# design.net
KiCad netlist of a schematic drawn in Altium Designer
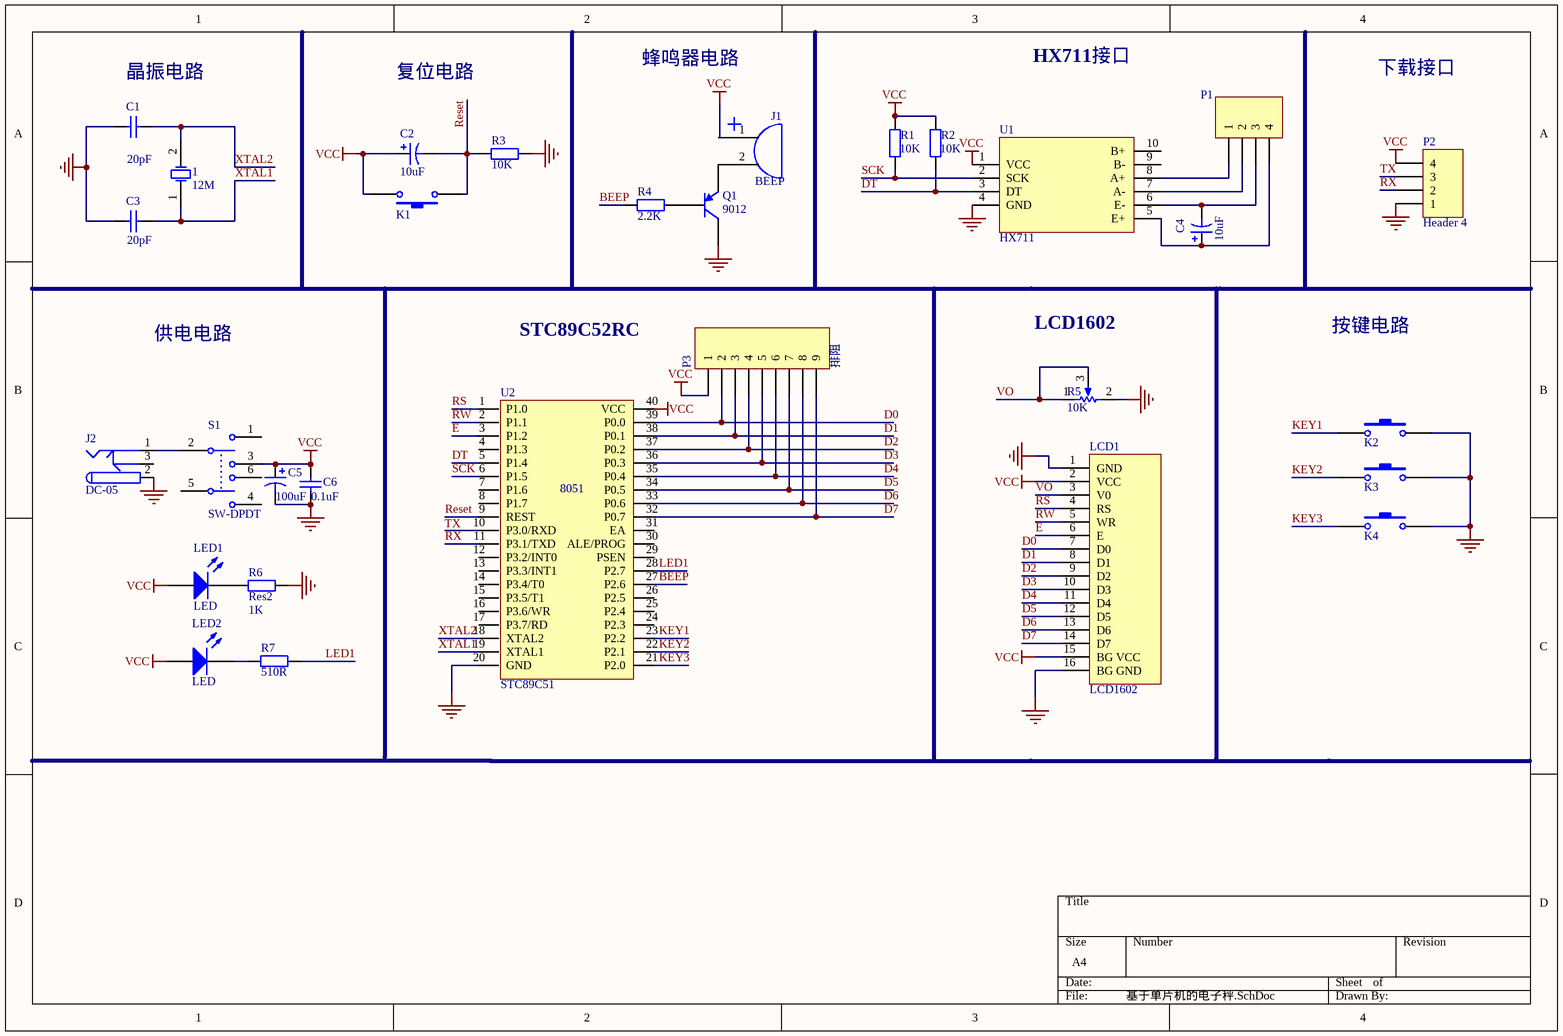
[diagram p0: 基于单片机的电子秤.SchDoc]

(export (version "E")
  (design (tool "Eeschema 10.0.6"))
  (components
    (comp (ref "1")
      (value "12M")
      (footprint "XTAL_US")
      (description "Crystal Oscillator")
      (fields (field (name "PUBLISHER") "Altium Limited"))
      (libsource (lib "Miscellaneous Devices") (part "XTAL"))
    )
    (comp (ref "C1")
      (value "20pF")
      (footprint "RAD-0.1")
      (description "Capacitor")
      (fields (field (name "Comment") "Cap") (field (name "PUBLISHER") "Altium Limited"))
      (libsource (lib "Miscellaneous Devices") (part "Cap"))
    )
    (comp (ref "C2")
      (value "10uF")
      (footprint "RB.1/.2")
      (description "Polarized Capacitor (Radial)")
      (fields (field (name "Comment") "Cap Pol1") (field (name "PUBLISHER") "Altium Limited"))
      (libsource (lib "Miscellaneous Devices") (part "Cap Pol1"))
    )
    (comp (ref "C3")
      (value "20pF")
      (footprint "RAD-0.1")
      (description "Capacitor")
      (fields (field (name "Comment") "Cap") (field (name "PUBLISHER") "Altium Limited"))
      (libsource (lib "Miscellaneous Devices") (part "Cap"))
    )
    (comp (ref "C4")
      (value "10uF")
      (footprint "RB7.6-15")
      (description "Polarized Capacitor (Radial)")
      (fields (field (name "Comment") "Cap Pol1") (field (name "PUBLISHER") "Altium Limited"))
      (libsource (lib "Miscellaneous Devices") (part "Cap Pol1"))
    )
    (comp (ref "C5")
      (value "100uF")
      (footprint "RB.1/.2")
      (description "Polarized Capacitor (Radial)")
      (fields (field (name "Comment") "Cap Pol1") (field (name "PUBLISHER") "Altium Limited"))
      (libsource (lib "Miscellaneous Devices") (part "Cap Pol1"))
    )
    (comp (ref "C6")
      (value "0.1uF")
      (footprint "RAD-0.1")
      (description "Capacitor")
      (fields (field (name "Comment") "Cap") (field (name "PUBLISHER") "Altium Limited"))
      (libsource (lib "Miscellaneous Devices") (part "Cap"))
    )
    (comp (ref "J1")
      (value "BEEP")
      (footprint "Beep")
      (description "蜂鸣器")
      (libsource (lib "Fszhang") (part "BEEP"))
    )
    (comp (ref "J2") (value "DC-05") (footprint "DC-05") (libsource (lib "My library") (part "DC-05")))
    (comp (ref "K1") (value "四脚按键") (footprint "四脚按键") (libsource (lib "My library") (part "四脚按键")))
    (comp (ref "K2") (value "四脚按键") (footprint "四脚按键") (libsource (lib "My library") (part "四脚按键")))
    (comp (ref "K3") (value "四脚按键") (footprint "四脚按键") (libsource (lib "My library") (part "四脚按键")))
    (comp (ref "K4") (value "四脚按键") (footprint "四脚按键") (libsource (lib "My library") (part "四脚按键")))
    (comp (ref "LCD1")
      (value "LCD1602")
      (footprint "LCD1602")
      (libsource (lib "My library") (part "LCD1602"))
    )
    (comp (ref "LED1") (value "LED") (footprint "LED") (libsource (lib "My library") (part "LED")))
    (comp (ref "LED2") (value "LED") (footprint "LED") (libsource (lib "My library") (part "LED")))
    (comp (ref "P1")
      (value "Header 4")
      (footprint "HDR4X1_B1")
      (description "接插件")
      (fields (field (name "PUBLISHER") "Altium Limited"))
      (libsource (lib "Fszhang") (part "Header 4"))
    )
    (comp (ref "P2")
      (value "Header 4")
      (footprint "HDR1X4")
      (description "Header, 4-Pin")
      (fields (field (name "PUBLISHER") "Altium Limited"))
      (libsource (lib "Miscellaneous Connectors") (part "Header 4"))
    )
    (comp (ref "P3")
      (value "排阻")
      (footprint "SIP9")
      (description "Header, 9-Pin")
      (fields (field (name "PUBLISHER") "Altium Limited"))
      (libsource (lib "Miscellaneous Connectors") (part "Header 9"))
    )
    (comp (ref "Q1")
      (value "9012")
      (footprint "TO-92A")
      (description "PNP General Purpose Amplifier")
      (fields (field (name "PUBLISHER") "Altium Limited"))
      (libsource (lib "Miscellaneous Devices") (part "2N3906"))
    )
    (comp (ref "R1")
      (value "10K")
      (footprint "AXIAL-0.4")
      (description "Resistor")
      (fields (field (name "Comment") "Res2") (field (name "PUBLISHER") "Altium Limited"))
      (libsource (lib "") (part "Res2_1"))
    )
    (comp (ref "R2")
      (value "10K")
      (footprint "AXIAL-0.4")
      (description "Resistor")
      (fields (field (name "Comment") "Res2") (field (name "PUBLISHER") "Altium Limited"))
      (libsource (lib "") (part "Res2_1"))
    )
    (comp (ref "R3")
      (value "10K")
      (footprint "AXIAL-0.4")
      (description "Resistor")
      (fields (field (name "Comment") "Res2") (field (name "PUBLISHER") "Altium Limited"))
      (libsource (lib "") (part "Res2_2"))
    )
    (comp (ref "R4")
      (value "2.2K")
      (footprint "AXIAL-0.4")
      (description "Resistor")
      (fields (field (name "Comment") "Res2") (field (name "PUBLISHER") "Altium Limited"))
      (libsource (lib "") (part "Res2_2"))
    )
    (comp (ref "R5")
      (value "10K")
      (footprint "RPot")
      (description "RPot")
      (libsource (lib "My library") (part "RPOT"))
    )
    (comp (ref "R6")
      (value "Res2")
      (footprint "AXIAL-0.4")
      (description "Resistor")
      (fields (field (name "ALTIUM_VALUE") "1K") (field (name "PUBLISHER") "Altium Limited"))
      (libsource (lib "Miscellaneous Devices") (part "Res2"))
    )
    (comp (ref "R7")
      (value "510R")
      (footprint "AXIAL-0.4")
      (description "Resistor")
      (fields (field (name "Comment") "Res2") (field (name "PUBLISHER") "Altium Limited"))
      (libsource (lib "") (part "Res2_2"))
    )
    (comp (ref "S1")
      (value "SW-DPDT")
      (footprint "SWITCH_B1")
      (description "单刀双掷开关")
      (fields (field (name "PUBLISHER") "Altium Limited"))
      (libsource (lib "Fszhang") (part "SW-DPDT"))
    )
    (comp (ref "U1") (value "HX711") (footprint "HX711") (libsource (lib "My library") (part "HX711")))
    (comp (ref "U2") (value "STC89C51") (footprint "DIP-40") (libsource (lib "My library") (part "STC89C51")))
  )
  (nets
    (net (code "1") (name "/BEEP") (class "Default")
      (node (ref "R4") (pin "2") (pinfunction "2_2") (pintype "passive"))
      (node (ref "U2") (pin "27") (pinfunction "P2.6_27") (pintype "passive"))
    )
    (net (code "2") (name "/D0") (class "Default")
      (node (ref "LCD1") (pin "7") (pinfunction "D0_7") (pintype "power_in"))
      (node (ref "P3") (pin "2") (pinfunction "2_2") (pintype "passive"))
      (node (ref "U2") (pin "39") (pinfunction "P0.0_39") (pintype "passive"))
    )
    (net (code "3") (name "/D1") (class "Default")
      (node (ref "LCD1") (pin "8") (pinfunction "D1_8") (pintype "power_in"))
      (node (ref "P3") (pin "3") (pinfunction "3_3") (pintype "passive"))
      (node (ref "U2") (pin "38") (pinfunction "P0.1_38") (pintype "passive"))
    )
    (net (code "4") (name "/D2") (class "Default")
      (node (ref "LCD1") (pin "9") (pinfunction "D2_9") (pintype "power_in"))
      (node (ref "P3") (pin "4") (pinfunction "4_4") (pintype "passive"))
      (node (ref "U2") (pin "37") (pinfunction "P0.2_37") (pintype "passive"))
    )
    (net (code "5") (name "/D3") (class "Default")
      (node (ref "LCD1") (pin "10") (pinfunction "D3_10") (pintype "power_in"))
      (node (ref "P3") (pin "5") (pinfunction "5_5") (pintype "passive"))
      (node (ref "U2") (pin "36") (pinfunction "P0.3_36") (pintype "passive"))
    )
    (net (code "6") (name "/D4") (class "Default")
      (node (ref "LCD1") (pin "11") (pinfunction "D4_11") (pintype "power_in"))
      (node (ref "P3") (pin "6") (pinfunction "6_6") (pintype "passive"))
      (node (ref "U2") (pin "35") (pinfunction "P0.4_35") (pintype "passive"))
    )
    (net (code "7") (name "/D5") (class "Default")
      (node (ref "LCD1") (pin "12") (pinfunction "D5_12") (pintype "power_in"))
      (node (ref "P3") (pin "7") (pinfunction "7_7") (pintype "passive"))
      (node (ref "U2") (pin "34") (pinfunction "P0.5_34") (pintype "passive"))
    )
    (net (code "8") (name "/D6") (class "Default")
      (node (ref "LCD1") (pin "13") (pinfunction "D6_13") (pintype "power_in"))
      (node (ref "P3") (pin "8") (pinfunction "8_8") (pintype "passive"))
      (node (ref "U2") (pin "33") (pinfunction "P0.6_33") (pintype "passive"))
    )
    (net (code "9") (name "/D7") (class "Default")
      (node (ref "LCD1") (pin "14") (pinfunction "D7_14") (pintype "power_in"))
      (node (ref "P3") (pin "9") (pinfunction "9_9") (pintype "passive"))
      (node (ref "U2") (pin "32") (pinfunction "P0.7_32") (pintype "passive"))
    )
    (net (code "10") (name "/DT") (class "Default")
      (node (ref "R2") (pin "2") (pinfunction "2_2") (pintype "passive"))
      (node (ref "U1") (pin "3") (pinfunction "DT_3") (pintype "passive"))
      (node (ref "U2") (pin "5") (pinfunction "P1.4_5") (pintype "passive"))
    )
    (net (code "11") (name "/E") (class "Default")
      (node (ref "LCD1") (pin "6") (pinfunction "E_6") (pintype "power_in"))
      (node (ref "U2") (pin "3") (pinfunction "P1.2_3") (pintype "passive"))
    )
    (net (code "12") (name "/KEY1") (class "Default")
      (node (ref "K2") (pin "2") (pinfunction "2_2") (pintype "passive"))
      (node (ref "U2") (pin "23") (pinfunction "P2.2_23") (pintype "passive"))
    )
    (net (code "13") (name "/KEY2") (class "Default")
      (node (ref "K3") (pin "2") (pinfunction "2_2") (pintype "passive"))
      (node (ref "U2") (pin "22") (pinfunction "P2.1_22") (pintype "passive"))
    )
    (net (code "14") (name "/KEY3") (class "Default")
      (node (ref "K4") (pin "2") (pinfunction "2_2") (pintype "passive"))
      (node (ref "U2") (pin "21") (pinfunction "P2.0_21") (pintype "passive"))
    )
    (net (code "15") (name "/LED1") (class "Default")
      (node (ref "R7") (pin "1") (pinfunction "1_1") (pintype "passive"))
      (node (ref "U2") (pin "28") (pinfunction "P2.7_28") (pintype "passive"))
    )
    (net (code "16") (name "/RS") (class "Default")
      (node (ref "LCD1") (pin "4") (pinfunction "RS_4") (pintype "power_in"))
      (node (ref "U2") (pin "1") (pinfunction "P1.0_1") (pintype "passive"))
    )
    (net (code "17") (name "/RW") (class "Default")
      (node (ref "LCD1") (pin "5") (pinfunction "WR_5") (pintype "power_in"))
      (node (ref "U2") (pin "2") (pinfunction "P1.1_2") (pintype "passive"))
    )
    (net (code "18") (name "/RX") (class "Default")
      (node (ref "P2") (pin "2") (pinfunction "2_2") (pintype "passive"))
      (node (ref "U2") (pin "11") (pinfunction "P3.1/TXD_11") (pintype "passive"))
    )
    (net (code "19") (name "/Reset") (class "Default")
      (node (ref "C2") (pin "2") (pinfunction "2_2") (pintype "passive"))
      (node (ref "K1") (pin "2") (pinfunction "2_2") (pintype "passive"))
      (node (ref "R3") (pin "2") (pinfunction "2_2") (pintype "passive"))
      (node (ref "U2") (pin "9") (pinfunction "REST_9") (pintype "passive"))
    )
    (net (code "20") (name "/SCK") (class "Default")
      (node (ref "R1") (pin "2") (pinfunction "2_2") (pintype "passive"))
      (node (ref "U1") (pin "2") (pinfunction "SCK_2") (pintype "passive"))
      (node (ref "U2") (pin "6") (pinfunction "P1.5_6") (pintype "passive"))
    )
    (net (code "21") (name "/TX") (class "Default")
      (node (ref "P2") (pin "3") (pinfunction "3_3") (pintype "passive"))
    )
    (net (code "22") (name "/VO") (class "Default")
      (node (ref "LCD1") (pin "3") (pinfunction "V0_3") (pintype "power_in"))
      (node (ref "R5") (pin "1") (pinfunction "1_1") (pintype "passive"))
      (node (ref "R5") (pin "3") (pinfunction "3_3") (pintype "passive"))
    )
    (net (code "23") (name "/XTAL1") (class "Default")
      (node (ref "1") (pin "1") (pinfunction "OSC1_1") (pintype "passive"))
      (node (ref "C3") (pin "1") (pinfunction "1_1") (pintype "passive"))
      (node (ref "U2") (pin "19") (pinfunction "XTAL1_19") (pintype "passive"))
    )
    (net (code "24") (name "/XTAL2") (class "Default")
      (node (ref "1") (pin "2") (pinfunction "OSC2_2") (pintype "passive"))
      (node (ref "C1") (pin "1") (pinfunction "1_1") (pintype "passive"))
      (node (ref "U2") (pin "18") (pinfunction "XTAL2_18") (pintype "passive"))
    )
    (net (code "25") (name "GND") (class "Default")
      (node (ref "C1") (pin "2") (pinfunction "2_2") (pintype "passive"))
      (node (ref "C3") (pin "2") (pinfunction "2_2") (pintype "passive"))
      (node (ref "C5") (pin "2") (pinfunction "2_2") (pintype "passive"))
      (node (ref "C6") (pin "1") (pinfunction "1_1") (pintype "passive"))
      (node (ref "J2") (pin "2") (pinfunction "2_2") (pintype "passive"))
      (node (ref "K2") (pin "1") (pinfunction "1_1") (pintype "passive"))
      (node (ref "K3") (pin "1") (pinfunction "1_1") (pintype "passive"))
      (node (ref "K4") (pin "1") (pinfunction "1_1") (pintype "passive"))
      (node (ref "LCD1") (pin "1") (pinfunction "GND_1") (pintype "power_in"))
      (node (ref "LCD1") (pin "16") (pinfunction "BG_GND_16") (pintype "power_in"))
      (node (ref "P2") (pin "1") (pinfunction "1_1") (pintype "passive"))
      (node (ref "Q1") (pin "3") (pinfunction "C_3") (pintype "passive"))
      (node (ref "R3") (pin "1") (pinfunction "1_1") (pintype "passive"))
      (node (ref "R5") (pin "2") (pinfunction "2_2") (pintype "passive"))
      (node (ref "R6") (pin "2") (pinfunction "2_2") (pintype "passive"))
      (node (ref "U1") (pin "4") (pinfunction "GND_4") (pintype "passive"))
      (node (ref "U2") (pin "20") (pinfunction "GND_20") (pintype "passive"))
    )
    (net (code "26") (name "Net-(J1-1)") (class "Default")
      (node (ref "J1") (pin "2") (pinfunction "1_2") (pintype "passive"))
      (node (ref "Q1") (pin "1") (pinfunction "E_1") (pintype "passive"))
    )
    (net (code "27") (name "Net-(J2-Pad1)") (class "Default")
      (node (ref "J2") (pin "1") (pinfunction "1_1") (pintype "passive"))
      (node (ref "S1") (pin "2") (pinfunction "2_2") (pintype "passive"))
    )
    (net (code "28") (name "Net-(LED1-Pad2)") (class "Default")
      (node (ref "LED1") (pin "2") (pinfunction "2_2") (pintype "passive"))
      (node (ref "R6") (pin "1") (pinfunction "1_1") (pintype "passive"))
    )
    (net (code "29") (name "Net-(LED2-Pad2)") (class "Default")
      (node (ref "LED2") (pin "2") (pinfunction "2_2") (pintype "passive"))
      (node (ref "R7") (pin "2") (pinfunction "2_2") (pintype "passive"))
    )
    (net (code "30") (name "Net-(Q1-B)") (class "Default")
      (node (ref "Q1") (pin "2") (pinfunction "B_2") (pintype "passive"))
      (node (ref "R4") (pin "1") (pinfunction "1_1") (pintype "passive"))
    )
    (net (code "31") (name "Net-(U1-A+)") (class "Default")
      (node (ref "P1") (pin "1") (pinfunction "1_1") (pintype "passive"))
      (node (ref "U1") (pin "8") (pinfunction "A+_8") (pintype "passive"))
    )
    (net (code "32") (name "Net-(U1-A-)") (class "Default")
      (node (ref "P1") (pin "2") (pinfunction "2_2") (pintype "passive"))
      (node (ref "U1") (pin "7") (pinfunction "A-_7") (pintype "passive"))
    )
    (net (code "33") (name "Net-(U1-E+)") (class "Default")
      (node (ref "C4") (pin "1") (pinfunction "1_1") (pintype "passive"))
      (node (ref "P1") (pin "4") (pinfunction "4_4") (pintype "passive"))
      (node (ref "U1") (pin "5") (pinfunction "E+_5") (pintype "passive"))
    )
    (net (code "34") (name "Net-(U1-E-)") (class "Default")
      (node (ref "C4") (pin "2") (pinfunction "2_2") (pintype "passive"))
      (node (ref "P1") (pin "3") (pinfunction "3_3") (pintype "passive"))
      (node (ref "U1") (pin "6") (pinfunction "E-_6") (pintype "passive"))
    )
    (net (code "35") (name "VCC") (class "Default")
      (node (ref "C2") (pin "1") (pinfunction "1_1") (pintype "passive"))
      (node (ref "C5") (pin "1") (pinfunction "1_1") (pintype "passive"))
      (node (ref "C6") (pin "2") (pinfunction "2_2") (pintype "passive"))
      (node (ref "J1") (pin "1") (pinfunction "0_1") (pintype "passive"))
      (node (ref "K1") (pin "1") (pinfunction "1_1") (pintype "passive"))
      (node (ref "LCD1") (pin "15") (pinfunction "BG_VCC_15") (pintype "power_in"))
      (node (ref "LCD1") (pin "2") (pinfunction "VCC_2") (pintype "power_in"))
      (node (ref "LED1") (pin "1") (pinfunction "1_1") (pintype "passive"))
      (node (ref "LED2") (pin "1") (pinfunction "1_1") (pintype "passive"))
      (node (ref "P2") (pin "4") (pinfunction "4_4") (pintype "passive"))
      (node (ref "P3") (pin "1") (pinfunction "1_1") (pintype "passive"))
      (node (ref "R1") (pin "1") (pinfunction "1_1") (pintype "passive"))
      (node (ref "R2") (pin "1") (pinfunction "1_1") (pintype "passive"))
      (node (ref "S1") (pin "3") (pinfunction "3_3") (pintype "passive"))
      (node (ref "U1") (pin "1") (pinfunction "VCC_1") (pintype "passive"))
      (node (ref "U2") (pin "40") (pinfunction "VCC_40") (pintype "passive"))
    )
    (net (code "36") (name "unconnected-(J2-Pad3)") (class "Default")
      (node (ref "J2") (pin "3") (pinfunction "3_3") (pintype "passive"))
    )
    (net (code "37") (name "unconnected-(S1-Pad1)") (class "Default")
      (node (ref "S1") (pin "1") (pinfunction "1_1") (pintype "passive"))
    )
    (net (code "38") (name "unconnected-(S1-Pad4)") (class "Default")
      (node (ref "S1") (pin "4") (pinfunction "4_4") (pintype "passive"))
    )
    (net (code "39") (name "unconnected-(S1-Pad5)") (class "Default")
      (node (ref "S1") (pin "5") (pinfunction "5_5") (pintype "passive"))
    )
    (net (code "40") (name "unconnected-(S1-Pad6)") (class "Default")
      (node (ref "S1") (pin "6") (pinfunction "6_6") (pintype "passive"))
    )
    (net (code "41") (name "unconnected-(U1-B+-Pad10)") (class "Default")
      (node (ref "U1") (pin "10") (pinfunction "B+_10") (pintype "passive"))
    )
    (net (code "42") (name "unconnected-(U1-B--Pad9)") (class "Default")
      (node (ref "U1") (pin "9") (pinfunction "B-_9") (pintype "passive"))
    )
    (net (code "43") (name "unconnected-(U2-ALE{slash}PROG-Pad30)") (class "Default")
      (node (ref "U2") (pin "30") (pinfunction "ALE/PROG_30") (pintype "passive"))
    )
    (net (code "44") (name "unconnected-(U2-EA-Pad31)") (class "Default")
      (node (ref "U2") (pin "31") (pinfunction "EA_31") (pintype "passive"))
    )
    (net (code "45") (name "unconnected-(U2-P1.3-Pad4)") (class "Default")
      (node (ref "U2") (pin "4") (pinfunction "P1.3_4") (pintype "passive"))
    )
    (net (code "46") (name "unconnected-(U2-P1.6-Pad7)") (class "Default")
      (node (ref "U2") (pin "7") (pinfunction "P1.6_7") (pintype "passive"))
    )
    (net (code "47") (name "unconnected-(U2-P1.7-Pad8)") (class "Default")
      (node (ref "U2") (pin "8") (pinfunction "P1.7_8") (pintype "passive"))
    )
    (net (code "48") (name "unconnected-(U2-P2.3-Pad24)") (class "Default")
      (node (ref "U2") (pin "24") (pinfunction "P2.3_24") (pintype "passive"))
    )
    (net (code "49") (name "unconnected-(U2-P2.4-Pad25)") (class "Default")
      (node (ref "U2") (pin "25") (pinfunction "P2.4_25") (pintype "passive"))
    )
    (net (code "50") (name "unconnected-(U2-P2.5-Pad26)") (class "Default")
      (node (ref "U2") (pin "26") (pinfunction "P2.5_26") (pintype "passive"))
    )
    (net (code "51") (name "unconnected-(U2-P3.0{slash}RXD-Pad10)") (class "Default")
      (node (ref "U2") (pin "10") (pinfunction "P3.0/RXD_10") (pintype "passive"))
    )
    (net (code "52") (name "unconnected-(U2-P3.2{slash}INT0-Pad12)") (class "Default")
      (node (ref "U2") (pin "12") (pinfunction "P3.2/INT0_12") (pintype "passive"))
    )
    (net (code "53") (name "unconnected-(U2-P3.3{slash}INT1-Pad13)") (class "Default")
      (node (ref "U2") (pin "13") (pinfunction "P3.3/INT1_13") (pintype "passive"))
    )
    (net (code "54") (name "unconnected-(U2-P3.4{slash}T0-Pad14)") (class "Default")
      (node (ref "U2") (pin "14") (pinfunction "P3.4/T0_14") (pintype "passive"))
    )
    (net (code "55") (name "unconnected-(U2-P3.5{slash}T1-Pad15)") (class "Default")
      (node (ref "U2") (pin "15") (pinfunction "P3.5/T1_15") (pintype "passive"))
    )
    (net (code "56") (name "unconnected-(U2-P3.6{slash}WR-Pad16)") (class "Default")
      (node (ref "U2") (pin "16") (pinfunction "P3.6/WR_16") (pintype "passive"))
    )
    (net (code "57") (name "unconnected-(U2-P3.7{slash}RD-Pad17)") (class "Default")
      (node (ref "U2") (pin "17") (pinfunction "P3.7/RD_17") (pintype "passive"))
    )
    (net (code "58") (name "unconnected-(U2-PSEN-Pad29)") (class "Default")
      (node (ref "U2") (pin "29") (pinfunction "PSEN_29") (pintype "passive"))
    )
  )
)
